# copy_from.net
KiCad netlist of a schematic drawn in EAGLE
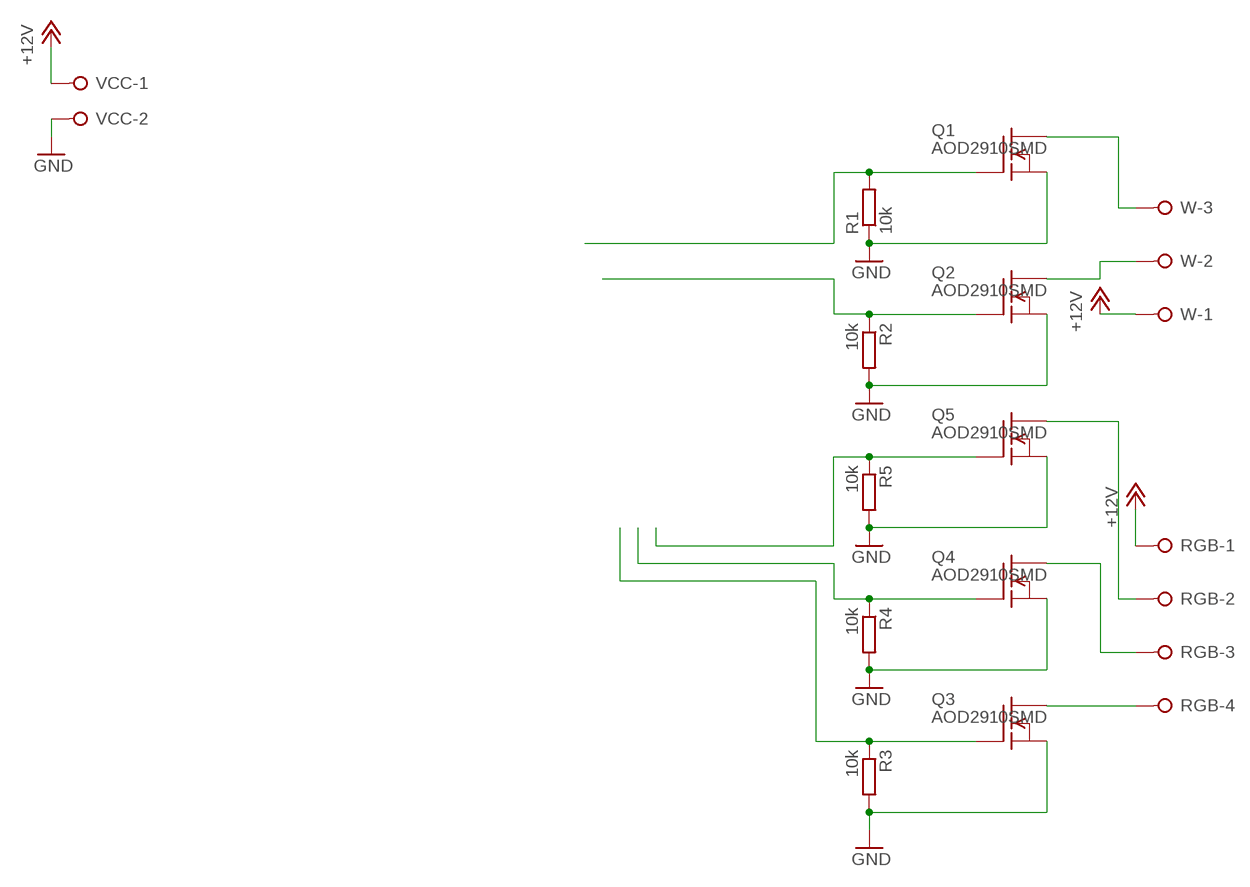
[diagram p0: schematic, sheet 1]

(export (version "E")
  (design (tool "Eeschema 10.0.6"))
  (components
    (comp (ref "Q1")
      (value "AOD2910SMD")
      (footprint "eagle-import:DPAK-3")
      (libsource (lib "eagle-import") (part "AOD2910SMD"))
    )
    (comp (ref "Q2")
      (value "AOD2910SMD")
      (footprint "eagle-import:DPAK-3")
      (libsource (lib "eagle-import") (part "AOD2910SMD"))
    )
    (comp (ref "Q3")
      (value "AOD2910SMD")
      (footprint "eagle-import:DPAK-3")
      (libsource (lib "eagle-import") (part "AOD2910SMD"))
    )
    (comp (ref "Q4")
      (value "AOD2910SMD")
      (footprint "eagle-import:DPAK-3")
      (libsource (lib "eagle-import") (part "AOD2910SMD"))
    )
    (comp (ref "Q5")
      (value "AOD2910SMD")
      (footprint "eagle-import:DPAK-3")
      (libsource (lib "eagle-import") (part "AOD2910SMD"))
    )
    (comp (ref "R1")
      (value "10k")
      (footprint "eagle-import:R0805")
      (libsource (lib "eagle-import") (part "R-EU_R0805"))
    )
    (comp (ref "R2")
      (value "10k")
      (footprint "eagle-import:R0805")
      (libsource (lib "eagle-import") (part "R-EU_R0805"))
    )
    (comp (ref "R3")
      (value "10k")
      (footprint "eagle-import:R0805")
      (libsource (lib "eagle-import") (part "R-EU_R0805"))
    )
    (comp (ref "R4")
      (value "10k")
      (footprint "eagle-import:R0805")
      (libsource (lib "eagle-import") (part "R-EU_R0805"))
    )
    (comp (ref "R5")
      (value "10k")
      (footprint "eagle-import:R0805")
      (libsource (lib "eagle-import") (part "R-EU_R0805"))
    )
    (comp (ref "RGB")
      (value "W237-04P")
      (footprint "eagle-import:W237-4P")
      (libsource (lib "eagle-import") (part "W237-04P"))
    )
    (comp (ref "VCC")
      (value "W237-02P")
      (footprint "eagle-import:W237-132")
      (libsource (lib "eagle-import") (part "W237-02P"))
    )
    (comp (ref "W")
      (value "W237-03P")
      (footprint "eagle-import:W237-133")
      (libsource (lib "eagle-import") (part "W237-03P"))
    )
  )
  (nets
    (net (code "1") (name "+12V") (class "Default")
      (node (ref "RGB") (pin "1") (pinfunction "KL_1") (pintype "passive"))
      (node (ref "VCC") (pin "1") (pinfunction "KL_1") (pintype "passive"))
      (node (ref "W") (pin "1") (pinfunction "KL_1") (pintype "passive"))
    )
    (net (code "2") (name "GND") (class "Default")
      (node (ref "Q1") (pin "3") (pinfunction "S_3") (pintype "passive"))
      (node (ref "Q2") (pin "3") (pinfunction "S_3") (pintype "passive"))
      (node (ref "Q3") (pin "3") (pinfunction "S_3") (pintype "passive"))
      (node (ref "Q4") (pin "3") (pinfunction "S_3") (pintype "passive"))
      (node (ref "Q5") (pin "3") (pinfunction "S_3") (pintype "passive"))
      (node (ref "R1") (pin "1") (pinfunction "1_1") (pintype "passive"))
      (node (ref "R2") (pin "2") (pinfunction "2_2") (pintype "passive"))
      (node (ref "R3") (pin "2") (pinfunction "2_2") (pintype "passive"))
      (node (ref "R4") (pin "2") (pinfunction "2_2") (pintype "passive"))
      (node (ref "R5") (pin "2") (pinfunction "2_2") (pintype "passive"))
      (node (ref "VCC") (pin "2") (pinfunction "KL_2") (pintype "passive"))
    )
    (net (code "3") (name "Net-(Q1-D)") (class "Default")
      (node (ref "Q1") (pin "4") (pinfunction "D_4") (pintype "passive"))
      (node (ref "W") (pin "3") (pinfunction "KL_3") (pintype "passive"))
    )
    (net (code "4") (name "Net-(Q1-G)") (class "Default")
      (node (ref "Q1") (pin "1") (pinfunction "G_1") (pintype "passive"))
      (node (ref "R1") (pin "2") (pinfunction "2_2") (pintype "passive"))
    )
    (net (code "5") (name "Net-(Q2-D)") (class "Default")
      (node (ref "Q2") (pin "4") (pinfunction "D_4") (pintype "passive"))
      (node (ref "W") (pin "2") (pinfunction "KL_2") (pintype "passive"))
    )
    (net (code "6") (name "Net-(Q2-G)") (class "Default")
      (node (ref "Q2") (pin "1") (pinfunction "G_1") (pintype "passive"))
      (node (ref "R2") (pin "1") (pinfunction "1_1") (pintype "passive"))
    )
    (net (code "7") (name "Net-(Q3-D)") (class "Default")
      (node (ref "Q3") (pin "4") (pinfunction "D_4") (pintype "passive"))
      (node (ref "RGB") (pin "4") (pinfunction "KL_4") (pintype "passive"))
    )
    (net (code "8") (name "Net-(Q3-G)") (class "Default")
      (node (ref "Q3") (pin "1") (pinfunction "G_1") (pintype "passive"))
      (node (ref "R3") (pin "1") (pinfunction "1_1") (pintype "passive"))
    )
    (net (code "9") (name "Net-(Q4-D)") (class "Default")
      (node (ref "Q4") (pin "4") (pinfunction "D_4") (pintype "passive"))
      (node (ref "RGB") (pin "3") (pinfunction "KL_3") (pintype "passive"))
    )
    (net (code "10") (name "Net-(Q4-G)") (class "Default")
      (node (ref "Q4") (pin "1") (pinfunction "G_1") (pintype "passive"))
      (node (ref "R4") (pin "1") (pinfunction "1_1") (pintype "passive"))
    )
    (net (code "11") (name "Net-(Q5-D)") (class "Default")
      (node (ref "Q5") (pin "4") (pinfunction "D_4") (pintype "passive"))
      (node (ref "RGB") (pin "2") (pinfunction "KL_2") (pintype "passive"))
    )
    (net (code "12") (name "Net-(Q5-G)") (class "Default")
      (node (ref "Q5") (pin "1") (pinfunction "G_1") (pintype "passive"))
      (node (ref "R5") (pin "1") (pinfunction "1_1") (pintype "passive"))
    )
  )
)
